# SureDSP_Breakout.net
KiCad netlist of a schematic drawn in EAGLE
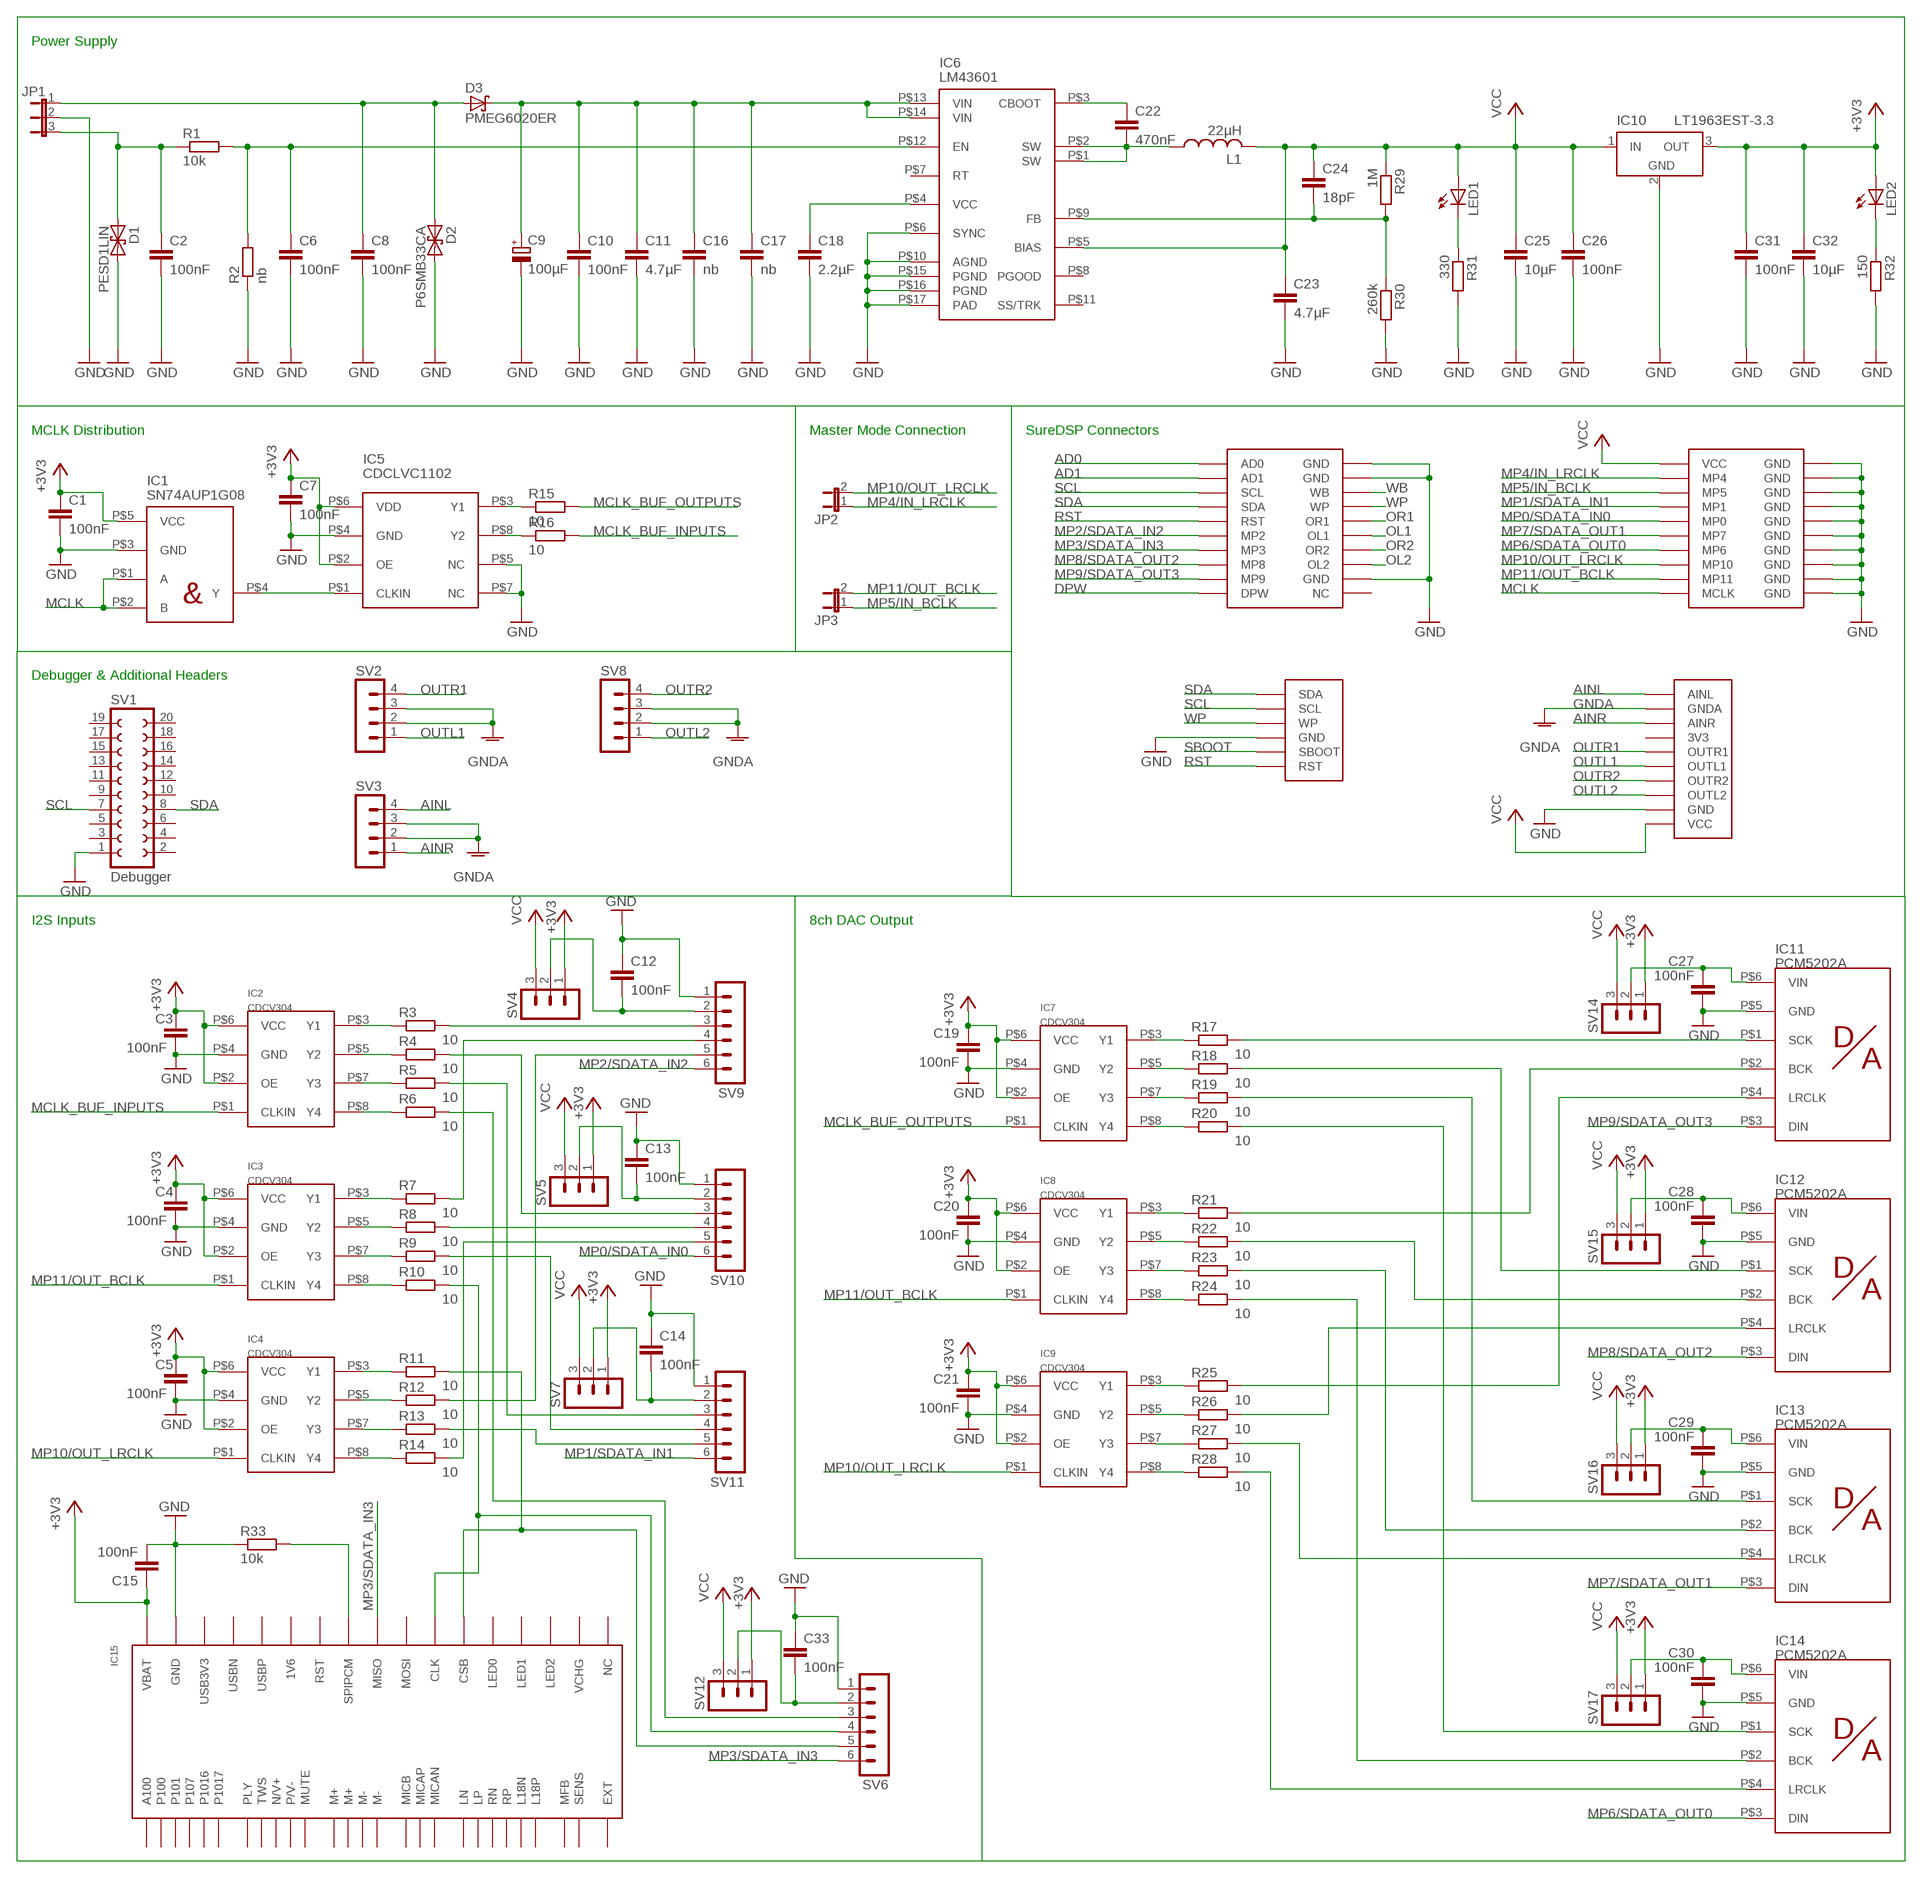
[diagram p0: schematic, sheet 1]

(export (version "E")
  (design (tool "Eeschema 10.0.6"))
  (components
    (comp (ref "C1")
      (value "100nF")
      (footprint "eagle-import:C0805K")
      (libsource (lib "eagle-import") (part "C-EUC0805K"))
    )
    (comp (ref "C2")
      (value "100nF")
      (footprint "eagle-import:C1210K")
      (libsource (lib "eagle-import") (part "C-EUC1210K"))
    )
    (comp (ref "C3")
      (value "100nF")
      (footprint "eagle-import:C0805K")
      (libsource (lib "eagle-import") (part "C-EUC0805K"))
    )
    (comp (ref "C4")
      (value "100nF")
      (footprint "eagle-import:C0805K")
      (libsource (lib "eagle-import") (part "C-EUC0805K"))
    )
    (comp (ref "C5")
      (value "100nF")
      (footprint "eagle-import:C0805K")
      (libsource (lib "eagle-import") (part "C-EUC0805K"))
    )
    (comp (ref "C6")
      (value "100nF")
      (footprint "eagle-import:C1210K")
      (libsource (lib "eagle-import") (part "C-EUC1210K"))
    )
    (comp (ref "C7")
      (value "100nF")
      (footprint "eagle-import:C0805K")
      (libsource (lib "eagle-import") (part "C-EUC0805K"))
    )
    (comp (ref "C8")
      (value "100nF")
      (footprint "eagle-import:C1210K")
      (libsource (lib "eagle-import") (part "C-EUC1210K"))
    )
    (comp (ref "C9")
      (value "100µF")
      (footprint "eagle-import:150CLZ-0810")
      (libsource (lib "eagle-import") (part "CPOL-EU150CLZ-0810"))
    )
    (comp (ref "C10")
      (value "100nF")
      (footprint "eagle-import:C1210K")
      (libsource (lib "eagle-import") (part "C-EUC1210K"))
    )
    (comp (ref "C11")
      (value "4.7µF")
      (footprint "eagle-import:C1210K")
      (libsource (lib "eagle-import") (part "C-EUC1210K"))
    )
    (comp (ref "C12")
      (value "100nF")
      (footprint "eagle-import:C0805K")
      (libsource (lib "eagle-import") (part "C-EUC0805K"))
    )
    (comp (ref "C13")
      (value "100nF")
      (footprint "eagle-import:C0805K")
      (libsource (lib "eagle-import") (part "C-EUC0805K"))
    )
    (comp (ref "C14")
      (value "100nF")
      (footprint "eagle-import:C0805K")
      (libsource (lib "eagle-import") (part "C-EUC0805K"))
    )
    (comp (ref "C15")
      (value "100nF")
      (footprint "eagle-import:C0805K")
      (libsource (lib "eagle-import") (part "C-EUC0805K"))
    )
    (comp (ref "C16")
      (value "nb")
      (footprint "eagle-import:C1210K")
      (libsource (lib "eagle-import") (part "C-EUC1210K"))
    )
    (comp (ref "C17")
      (value "nb")
      (footprint "eagle-import:C1210K")
      (libsource (lib "eagle-import") (part "C-EUC1210K"))
    )
    (comp (ref "C18")
      (value "2.2µF")
      (footprint "eagle-import:C0805K")
      (libsource (lib "eagle-import") (part "C-EUC0805K"))
    )
    (comp (ref "C19")
      (value "100nF")
      (footprint "eagle-import:C0805K")
      (libsource (lib "eagle-import") (part "C-EUC0805K"))
    )
    (comp (ref "C20")
      (value "100nF")
      (footprint "eagle-import:C0805K")
      (libsource (lib "eagle-import") (part "C-EUC0805K"))
    )
    (comp (ref "C21")
      (value "100nF")
      (footprint "eagle-import:C0805K")
      (libsource (lib "eagle-import") (part "C-EUC0805K"))
    )
    (comp (ref "C22")
      (value "470nF")
      (footprint "eagle-import:C0805K")
      (libsource (lib "eagle-import") (part "C-EUC0805K"))
    )
    (comp (ref "C23")
      (value "4.7µF")
      (footprint "eagle-import:C0805K")
      (libsource (lib "eagle-import") (part "C-EUC0805K"))
    )
    (comp (ref "C24")
      (value "18pF")
      (footprint "eagle-import:C0805K")
      (libsource (lib "eagle-import") (part "C-EUC0805K"))
    )
    (comp (ref "C25")
      (value "10µF")
      (footprint "eagle-import:C1210K")
      (libsource (lib "eagle-import") (part "C-EUC1210K"))
    )
    (comp (ref "C26")
      (value "100nF")
      (footprint "eagle-import:C0805K")
      (libsource (lib "eagle-import") (part "C-EUC0805K"))
    )
    (comp (ref "C27")
      (value "100nF")
      (footprint "eagle-import:C0805K")
      (libsource (lib "eagle-import") (part "C-EUC0805K"))
    )
    (comp (ref "C28")
      (value "100nF")
      (footprint "eagle-import:C0805K")
      (libsource (lib "eagle-import") (part "C-EUC0805K"))
    )
    (comp (ref "C29")
      (value "100nF")
      (footprint "eagle-import:C0805K")
      (libsource (lib "eagle-import") (part "C-EUC0805K"))
    )
    (comp (ref "C30")
      (value "100nF")
      (footprint "eagle-import:C0805K")
      (libsource (lib "eagle-import") (part "C-EUC0805K"))
    )
    (comp (ref "C31")
      (value "100nF")
      (footprint "eagle-import:C0805K")
      (libsource (lib "eagle-import") (part "C-EUC0805K"))
    )
    (comp (ref "C32")
      (value "10µF")
      (footprint "eagle-import:C1210K")
      (libsource (lib "eagle-import") (part "C-EUC1210K"))
    )
    (comp (ref "C33")
      (value "100nF")
      (footprint "eagle-import:C0805K")
      (libsource (lib "eagle-import") (part "C-EUC0805K"))
    )
    (comp (ref "D1")
      (value "PESD1LIN")
      (footprint "eagle-import:PESD1LIN")
      (libsource (lib "eagle-import") (part "PESD1LIN"))
    )
    (comp (ref "D2")
      (value "P6SMB33CA")
      (footprint "eagle-import:P6SMB")
      (libsource (lib "eagle-import") (part "P6SMB33CA"))
    )
    (comp (ref "D3")
      (value "PMEG6020ER")
      (footprint "eagle-import:PMEG6020ER")
      (libsource (lib "eagle-import") (part "PMEG6020ER"))
    )
    (comp (ref "IC1")
      (value "SN74AUP1G08")
      (footprint "eagle-import:SN74AUP1G08")
      (libsource (lib "eagle-import") (part "SN74AUP1G08"))
    )
    (comp (ref "IC2")
      (value "CDCV304")
      (footprint "eagle-import:CDCV304")
      (libsource (lib "eagle-import") (part "CDCV304"))
    )
    (comp (ref "IC3")
      (value "CDCV304")
      (footprint "eagle-import:CDCV304")
      (libsource (lib "eagle-import") (part "CDCV304"))
    )
    (comp (ref "IC4")
      (value "CDCV304")
      (footprint "eagle-import:CDCV304")
      (libsource (lib "eagle-import") (part "CDCV304"))
    )
    (comp (ref "IC5")
      (value "CDCLVC1102")
      (footprint "eagle-import:CDCLVC1102")
      (libsource (lib "eagle-import") (part "CDCLVC1102"))
    )
    (comp (ref "IC6")
      (value "LM43601")
      (footprint "eagle-import:LM43601")
      (libsource (lib "eagle-import") (part "LM43601"))
    )
    (comp (ref "IC7")
      (value "CDCV304")
      (footprint "eagle-import:CDCV304")
      (libsource (lib "eagle-import") (part "CDCV304"))
    )
    (comp (ref "IC8")
      (value "CDCV304")
      (footprint "eagle-import:CDCV304")
      (libsource (lib "eagle-import") (part "CDCV304"))
    )
    (comp (ref "IC9")
      (value "CDCV304")
      (footprint "eagle-import:CDCV304")
      (libsource (lib "eagle-import") (part "CDCV304"))
    )
    (comp (ref "IC10")
      (value "LT1963EST-3.3")
      (footprint "eagle-import:SOT223")
      (libsource (lib "eagle-import") (part "LT1963EST-3.3"))
    )
    (comp (ref "IC11")
      (value "PCM5202A")
      (footprint "eagle-import:PCM5202A")
      (libsource (lib "eagle-import") (part "PCM5202A"))
    )
    (comp (ref "IC12")
      (value "PCM5202A")
      (footprint "eagle-import:PCM5202A")
      (libsource (lib "eagle-import") (part "PCM5202A"))
    )
    (comp (ref "IC13")
      (value "PCM5202A")
      (footprint "eagle-import:PCM5202A")
      (libsource (lib "eagle-import") (part "PCM5202A"))
    )
    (comp (ref "IC14")
      (value "PCM5202A")
      (footprint "eagle-import:PCM5202A")
      (libsource (lib "eagle-import") (part "PCM5202A"))
    )
    (comp (ref "IC15")
      (value "CSRA64215")
      (footprint "eagle-import:CSRA64215")
      (libsource (lib "eagle-import") (part "CSRA64215"))
    )
    (comp (ref "IC16")
      (value "SUREDSP")
      (footprint "eagle-import:SUREDSP")
      (libsource (lib "eagle-import") (part "SUREDSP"))
    )
    (comp (ref "JP1")
      (value "JP2E")
      (footprint "eagle-import:JP2")
      (libsource (lib "eagle-import") (part "JP2E"))
    )
    (comp (ref "JP2")
      (value "JP1E")
      (footprint "eagle-import:JP1")
      (libsource (lib "eagle-import") (part "JP1E"))
    )
    (comp (ref "JP3")
      (value "JP1E")
      (footprint "eagle-import:JP1")
      (libsource (lib "eagle-import") (part "JP1E"))
    )
    (comp (ref "L1")
      (value "22µH")
      (footprint "eagle-import:L5650M")
      (libsource (lib "eagle-import") (part "L-USL5650M"))
    )
    (comp (ref "LED1")
      (value "LEDSML0805")
      (footprint "eagle-import:SML0805")
      (libsource (lib "eagle-import") (part "LEDSML0805"))
    )
    (comp (ref "LED2")
      (value "LEDSML0805")
      (footprint "eagle-import:SML0805")
      (libsource (lib "eagle-import") (part "LEDSML0805"))
    )
    (comp (ref "R1")
      (value "10k")
      (footprint "eagle-import:R2012")
      (libsource (lib "eagle-import") (part "R-EU_R2012"))
    )
    (comp (ref "R2")
      (value "nb")
      (footprint "eagle-import:R2012")
      (libsource (lib "eagle-import") (part "R-EU_R2012"))
    )
    (comp (ref "R3")
      (value "10")
      (footprint "eagle-import:R2012")
      (libsource (lib "eagle-import") (part "R-EU_R2012"))
    )
    (comp (ref "R4")
      (value "10")
      (footprint "eagle-import:R2012")
      (libsource (lib "eagle-import") (part "R-EU_R2012"))
    )
    (comp (ref "R5")
      (value "10")
      (footprint "eagle-import:R2012")
      (libsource (lib "eagle-import") (part "R-EU_R2012"))
    )
    (comp (ref "R6")
      (value "10")
      (footprint "eagle-import:R2012")
      (libsource (lib "eagle-import") (part "R-EU_R2012"))
    )
    (comp (ref "R7")
      (value "10")
      (footprint "eagle-import:R2012")
      (libsource (lib "eagle-import") (part "R-EU_R2012"))
    )
    (comp (ref "R8")
      (value "10")
      (footprint "eagle-import:R2012")
      (libsource (lib "eagle-import") (part "R-EU_R2012"))
    )
    (comp (ref "R9")
      (value "10")
      (footprint "eagle-import:R2012")
      (libsource (lib "eagle-import") (part "R-EU_R2012"))
    )
    (comp (ref "R10")
      (value "10")
      (footprint "eagle-import:R2012")
      (libsource (lib "eagle-import") (part "R-EU_R2012"))
    )
    (comp (ref "R11")
      (value "10")
      (footprint "eagle-import:R2012")
      (libsource (lib "eagle-import") (part "R-EU_R2012"))
    )
    (comp (ref "R12")
      (value "10")
      (footprint "eagle-import:R2012")
      (libsource (lib "eagle-import") (part "R-EU_R2012"))
    )
    (comp (ref "R13")
      (value "10")
      (footprint "eagle-import:R2012")
      (libsource (lib "eagle-import") (part "R-EU_R2012"))
    )
    (comp (ref "R14")
      (value "10")
      (footprint "eagle-import:R2012")
      (libsource (lib "eagle-import") (part "R-EU_R2012"))
    )
    (comp (ref "R15")
      (value "10")
      (footprint "eagle-import:R2012")
      (libsource (lib "eagle-import") (part "R-EU_R2012"))
    )
    (comp (ref "R16")
      (value "10")
      (footprint "eagle-import:R2012")
      (libsource (lib "eagle-import") (part "R-EU_R2012"))
    )
    (comp (ref "R17")
      (value "10")
      (footprint "eagle-import:R2012")
      (libsource (lib "eagle-import") (part "R-EU_R2012"))
    )
    (comp (ref "R18")
      (value "10")
      (footprint "eagle-import:R2012")
      (libsource (lib "eagle-import") (part "R-EU_R2012"))
    )
    (comp (ref "R19")
      (value "10")
      (footprint "eagle-import:R2012")
      (libsource (lib "eagle-import") (part "R-EU_R2012"))
    )
    (comp (ref "R20")
      (value "10")
      (footprint "eagle-import:R2012")
      (libsource (lib "eagle-import") (part "R-EU_R2012"))
    )
    (comp (ref "R21")
      (value "10")
      (footprint "eagle-import:R2012")
      (libsource (lib "eagle-import") (part "R-EU_R2012"))
    )
    (comp (ref "R22")
      (value "10")
      (footprint "eagle-import:R2012")
      (libsource (lib "eagle-import") (part "R-EU_R2012"))
    )
    (comp (ref "R23")
      (value "10")
      (footprint "eagle-import:R2012")
      (libsource (lib "eagle-import") (part "R-EU_R2012"))
    )
    (comp (ref "R24")
      (value "10")
      (footprint "eagle-import:R2012")
      (libsource (lib "eagle-import") (part "R-EU_R2012"))
    )
    (comp (ref "R25")
      (value "10")
      (footprint "eagle-import:R2012")
      (libsource (lib "eagle-import") (part "R-EU_R2012"))
    )
    (comp (ref "R26")
      (value "10")
      (footprint "eagle-import:R2012")
      (libsource (lib "eagle-import") (part "R-EU_R2012"))
    )
    (comp (ref "R27")
      (value "10")
      (footprint "eagle-import:R2012")
      (libsource (lib "eagle-import") (part "R-EU_R2012"))
    )
    (comp (ref "R28")
      (value "10")
      (footprint "eagle-import:R2012")
      (libsource (lib "eagle-import") (part "R-EU_R2012"))
    )
    (comp (ref "R29")
      (value "1M")
      (footprint "eagle-import:R2012")
      (libsource (lib "eagle-import") (part "R-EU_R2012"))
    )
    (comp (ref "R30")
      (value "260k")
      (footprint "eagle-import:R2012")
      (libsource (lib "eagle-import") (part "R-EU_R2012"))
    )
    (comp (ref "R31")
      (value "330")
      (footprint "eagle-import:R2012")
      (libsource (lib "eagle-import") (part "R-EU_R2012"))
    )
    (comp (ref "R32")
      (value "150")
      (footprint "eagle-import:R2012")
      (libsource (lib "eagle-import") (part "R-EU_R2012"))
    )
    (comp (ref "R33")
      (value "10k")
      (footprint "eagle-import:R2012")
      (libsource (lib "eagle-import") (part "R-EU_R2012"))
    )
    (comp (ref "SV1")
      (value "Debugger")
      (footprint "eagle-import:FE10-2")
      (libsource (lib "eagle-import") (part "FE10-2"))
    )
    (comp (ref "SV2")
      (value "MA04-1")
      (footprint "eagle-import:MA04-1")
      (libsource (lib "eagle-import") (part "MA04-1"))
    )
    (comp (ref "SV3")
      (value "MA04-1")
      (footprint "eagle-import:MA04-1")
      (libsource (lib "eagle-import") (part "MA04-1"))
    )
    (comp (ref "SV4")
      (value "MA03-1")
      (footprint "eagle-import:MA03-1")
      (libsource (lib "eagle-import") (part "MA03-1"))
    )
    (comp (ref "SV5")
      (value "MA03-1")
      (footprint "eagle-import:MA03-1")
      (libsource (lib "eagle-import") (part "MA03-1"))
    )
    (comp (ref "SV6")
      (value "MA06-1")
      (footprint "eagle-import:MA06-1")
      (libsource (lib "eagle-import") (part "MA06-1"))
    )
    (comp (ref "SV7")
      (value "MA03-1")
      (footprint "eagle-import:MA03-1")
      (libsource (lib "eagle-import") (part "MA03-1"))
    )
    (comp (ref "SV8")
      (value "MA04-1")
      (footprint "eagle-import:MA04-1")
      (libsource (lib "eagle-import") (part "MA04-1"))
    )
    (comp (ref "SV9")
      (value "MA06-1")
      (footprint "eagle-import:MA06-1")
      (libsource (lib "eagle-import") (part "MA06-1"))
    )
    (comp (ref "SV10")
      (value "MA06-1")
      (footprint "eagle-import:MA06-1")
      (libsource (lib "eagle-import") (part "MA06-1"))
    )
    (comp (ref "SV11")
      (value "MA06-1")
      (footprint "eagle-import:MA06-1")
      (libsource (lib "eagle-import") (part "MA06-1"))
    )
    (comp (ref "SV12")
      (value "MA03-1")
      (footprint "eagle-import:MA03-1")
      (libsource (lib "eagle-import") (part "MA03-1"))
    )
    (comp (ref "SV14")
      (value "MA03-1")
      (footprint "eagle-import:MA03-1")
      (libsource (lib "eagle-import") (part "MA03-1"))
    )
    (comp (ref "SV15")
      (value "MA03-1")
      (footprint "eagle-import:MA03-1")
      (libsource (lib "eagle-import") (part "MA03-1"))
    )
    (comp (ref "SV16")
      (value "MA03-1")
      (footprint "eagle-import:MA03-1")
      (libsource (lib "eagle-import") (part "MA03-1"))
    )
    (comp (ref "SV17")
      (value "MA03-1")
      (footprint "eagle-import:MA03-1")
      (libsource (lib "eagle-import") (part "MA03-1"))
    )
  )
  (nets
    (net (code "1") (name "+3V3") (class "Default")
      (node (ref "C1") (pin "1") (pinfunction "1_1") (pintype "passive"))
      (node (ref "C15") (pin "1") (pinfunction "1_1") (pintype "passive"))
      (node (ref "C19") (pin "1") (pinfunction "1_1") (pintype "passive"))
      (node (ref "C20") (pin "1") (pinfunction "1_1") (pintype "passive"))
      (node (ref "C21") (pin "1") (pinfunction "1_1") (pintype "passive"))
      (node (ref "C3") (pin "1") (pinfunction "1_1") (pintype "passive"))
      (node (ref "C31") (pin "1") (pinfunction "1_1") (pintype "passive"))
      (node (ref "C32") (pin "1") (pinfunction "1_1") (pintype "passive"))
      (node (ref "C4") (pin "1") (pinfunction "1_1") (pintype "passive"))
      (node (ref "C5") (pin "1") (pinfunction "1_1") (pintype "passive"))
      (node (ref "C7") (pin "1") (pinfunction "1_1") (pintype "passive"))
      (node (ref "IC1") (pin "P$5") (pinfunction "VCC_P$5") (pintype "bidirectional"))
      (node (ref "IC10") (pin "3") (pinfunction "OUT_3") (pintype "output"))
      (node (ref "IC15") (pin "P$5") (pinfunction "VBAT_P$5") (pintype "bidirectional"))
      (node (ref "IC2") (pin "P$2") (pinfunction "OE_P$2") (pintype "bidirectional"))
      (node (ref "IC2") (pin "P$6") (pinfunction "VCC_P$6") (pintype "bidirectional"))
      (node (ref "IC3") (pin "P$2") (pinfunction "OE_P$2") (pintype "bidirectional"))
      (node (ref "IC3") (pin "P$6") (pinfunction "VCC_P$6") (pintype "bidirectional"))
      (node (ref "IC4") (pin "P$2") (pinfunction "OE_P$2") (pintype "bidirectional"))
      (node (ref "IC4") (pin "P$6") (pinfunction "VCC_P$6") (pintype "bidirectional"))
      (node (ref "IC5") (pin "P$2") (pinfunction "OE_P$2") (pintype "bidirectional"))
      (node (ref "IC5") (pin "P$6") (pinfunction "VDD_P$6") (pintype "bidirectional"))
      (node (ref "IC7") (pin "P$2") (pinfunction "OE_P$2") (pintype "bidirectional"))
      (node (ref "IC7") (pin "P$6") (pinfunction "VCC_P$6") (pintype "bidirectional"))
      (node (ref "IC8") (pin "P$2") (pinfunction "OE_P$2") (pintype "bidirectional"))
      (node (ref "IC8") (pin "P$6") (pinfunction "VCC_P$6") (pintype "bidirectional"))
      (node (ref "IC9") (pin "P$2") (pinfunction "OE_P$2") (pintype "bidirectional"))
      (node (ref "IC9") (pin "P$6") (pinfunction "VCC_P$6") (pintype "bidirectional"))
      (node (ref "LED2") (pin "A") (pinfunction "A_A") (pintype "passive"))
      (node (ref "SV12") (pin "1") (pinfunction "1_1") (pintype "passive"))
      (node (ref "SV14") (pin "1") (pinfunction "1_1") (pintype "passive"))
      (node (ref "SV15") (pin "1") (pinfunction "1_1") (pintype "passive"))
      (node (ref "SV16") (pin "1") (pinfunction "1_1") (pintype "passive"))
      (node (ref "SV17") (pin "1") (pinfunction "1_1") (pintype "passive"))
      (node (ref "SV4") (pin "1") (pinfunction "1_1") (pintype "passive"))
      (node (ref "SV5") (pin "1") (pinfunction "1_1") (pintype "passive"))
      (node (ref "SV7") (pin "1") (pinfunction "1_1") (pintype "passive"))
    )
    (net (code "2") (name "/AD0") (class "Default")
      (node (ref "IC16") (pin "AD0") (pinfunction "AD0_AD0") (pintype "bidirectional"))
    )
    (net (code "3") (name "/AD1") (class "Default")
      (node (ref "IC16") (pin "AD1") (pinfunction "AD1_AD1") (pintype "bidirectional"))
    )
    (net (code "4") (name "/AINL") (class "Default")
      (node (ref "IC16") (pin "AINL") (pinfunction "AINL_AINL") (pintype "bidirectional"))
      (node (ref "SV3") (pin "4") (pinfunction "4_4") (pintype "passive"))
    )
    (net (code "5") (name "/AINR") (class "Default")
      (node (ref "IC16") (pin "AINR") (pinfunction "AINR_AINR") (pintype "bidirectional"))
      (node (ref "SV3") (pin "1") (pinfunction "1_1") (pintype "passive"))
    )
    (net (code "6") (name "/DPW") (class "Default")
      (node (ref "IC16") (pin "DPW") (pinfunction "DPW_DPW") (pintype "bidirectional"))
    )
    (net (code "7") (name "/MCLK") (class "Default")
      (node (ref "IC1") (pin "P$1") (pinfunction "A_P$1") (pintype "bidirectional"))
      (node (ref "IC1") (pin "P$2") (pinfunction "B_P$2") (pintype "bidirectional"))
      (node (ref "IC16") (pin "MCLK") (pinfunction "MCLK_MCLK") (pintype "bidirectional"))
    )
    (net (code "8") (name "/MCLK_BUF_INPUTS") (class "Default")
      (node (ref "IC2") (pin "P$1") (pinfunction "CLKIN_P$1") (pintype "bidirectional"))
      (node (ref "R16") (pin "2") (pinfunction "2_2") (pintype "passive"))
    )
    (net (code "9") (name "/MCLK_BUF_OUTPUTS") (class "Default")
      (node (ref "IC7") (pin "P$1") (pinfunction "CLKIN_P$1") (pintype "bidirectional"))
      (node (ref "R15") (pin "2") (pinfunction "2_2") (pintype "passive"))
    )
    (net (code "10") (name "/MP0{slash}SDATA_IN0") (class "Default")
      (node (ref "IC16") (pin "MP0") (pinfunction "MP0_MP0") (pintype "bidirectional"))
      (node (ref "SV10") (pin "6") (pinfunction "6_6") (pintype "passive"))
    )
    (net (code "11") (name "/MP1{slash}SDATA_IN1") (class "Default")
      (node (ref "IC16") (pin "MP1") (pinfunction "MP1_MP1") (pintype "bidirectional"))
      (node (ref "SV11") (pin "6") (pinfunction "6_6") (pintype "passive"))
    )
    (net (code "12") (name "/MP2{slash}SDATA_IN2") (class "Default")
      (node (ref "IC16") (pin "MP2") (pinfunction "MP2_MP2") (pintype "bidirectional"))
      (node (ref "SV9") (pin "6") (pinfunction "6_6") (pintype "passive"))
    )
    (net (code "13") (name "/MP3{slash}SDATA_IN3") (class "Default")
      (node (ref "IC15") (pin "P$7") (pinfunction "MISO_P$7") (pintype "bidirectional"))
      (node (ref "IC16") (pin "MP3") (pinfunction "MP3_MP3") (pintype "bidirectional"))
      (node (ref "SV6") (pin "6") (pinfunction "6_6") (pintype "passive"))
    )
    (net (code "14") (name "/MP4{slash}IN_LRCLK") (class "Default")
      (node (ref "IC16") (pin "MP4") (pinfunction "MP4_MP4") (pintype "bidirectional"))
      (node (ref "JP2") (pin "1") (pinfunction "1_1") (pintype "passive"))
    )
    (net (code "15") (name "/MP5{slash}IN_BCLK") (class "Default")
      (node (ref "IC16") (pin "MP5") (pinfunction "MP5_MP5") (pintype "bidirectional"))
      (node (ref "JP3") (pin "1") (pinfunction "1_1") (pintype "passive"))
    )
    (net (code "16") (name "/MP6{slash}SDATA_OUT0") (class "Default")
      (node (ref "IC14") (pin "P$3") (pinfunction "DIN_P$3") (pintype "bidirectional"))
      (node (ref "IC16") (pin "MP6") (pinfunction "MP6_MP6") (pintype "bidirectional"))
    )
    (net (code "17") (name "/MP7{slash}SDATA_OUT1") (class "Default")
      (node (ref "IC13") (pin "P$3") (pinfunction "DIN_P$3") (pintype "bidirectional"))
      (node (ref "IC16") (pin "MP7") (pinfunction "MP7_MP7") (pintype "bidirectional"))
    )
    (net (code "18") (name "/MP8{slash}SDATA_OUT2") (class "Default")
      (node (ref "IC12") (pin "P$3") (pinfunction "DIN_P$3") (pintype "bidirectional"))
      (node (ref "IC16") (pin "MP8") (pinfunction "MP8_MP8") (pintype "bidirectional"))
    )
    (net (code "19") (name "/MP9{slash}SDATA_OUT3") (class "Default")
      (node (ref "IC11") (pin "P$3") (pinfunction "DIN_P$3") (pintype "bidirectional"))
      (node (ref "IC16") (pin "MP9") (pinfunction "MP9_MP9") (pintype "bidirectional"))
    )
    (net (code "20") (name "/MP10{slash}OUT_LRCLK") (class "Default")
      (node (ref "IC16") (pin "MP10") (pinfunction "MP10_MP10") (pintype "bidirectional"))
      (node (ref "IC4") (pin "P$1") (pinfunction "CLKIN_P$1") (pintype "bidirectional"))
      (node (ref "IC9") (pin "P$1") (pinfunction "CLKIN_P$1") (pintype "bidirectional"))
      (node (ref "JP2") (pin "2") (pinfunction "2_2") (pintype "passive"))
    )
    (net (code "21") (name "/MP11{slash}OUT_BCLK") (class "Default")
      (node (ref "IC16") (pin "MP11") (pinfunction "MP11_MP11") (pintype "bidirectional"))
      (node (ref "IC3") (pin "P$1") (pinfunction "CLKIN_P$1") (pintype "bidirectional"))
      (node (ref "IC8") (pin "P$1") (pinfunction "CLKIN_P$1") (pintype "bidirectional"))
      (node (ref "JP3") (pin "2") (pinfunction "2_2") (pintype "passive"))
    )
    (net (code "22") (name "/OL1") (class "Default")
      (node (ref "IC16") (pin "OL1") (pinfunction "OL1_OL1") (pintype "bidirectional"))
    )
    (net (code "23") (name "/OL2") (class "Default")
      (node (ref "IC16") (pin "OL2") (pinfunction "OL2_OL2") (pintype "bidirectional"))
    )
    (net (code "24") (name "/OR1") (class "Default")
      (node (ref "IC16") (pin "OR1") (pinfunction "OR1_OR1") (pintype "bidirectional"))
    )
    (net (code "25") (name "/OR2") (class "Default")
      (node (ref "IC16") (pin "OR2") (pinfunction "OR2_OR2") (pintype "bidirectional"))
    )
    (net (code "26") (name "/OUTL1") (class "Default")
      (node (ref "IC16") (pin "OUTL1") (pinfunction "OUTL1_OUTL1") (pintype "bidirectional"))
      (node (ref "SV2") (pin "1") (pinfunction "1_1") (pintype "passive"))
    )
    (net (code "27") (name "/OUTL2") (class "Default")
      (node (ref "IC16") (pin "OUTL2") (pinfunction "OUTL2_OUTL2") (pintype "bidirectional"))
      (node (ref "SV8") (pin "1") (pinfunction "1_1") (pintype "passive"))
    )
    (net (code "28") (name "/OUTR1") (class "Default")
      (node (ref "IC16") (pin "OUTR1") (pinfunction "OUTR1_OUTR1") (pintype "bidirectional"))
      (node (ref "SV2") (pin "4") (pinfunction "4_4") (pintype "passive"))
    )
    (net (code "29") (name "/OUTR2") (class "Default")
      (node (ref "IC16") (pin "OUTR2") (pinfunction "OUTR2_OUTR2") (pintype "bidirectional"))
      (node (ref "SV8") (pin "4") (pinfunction "4_4") (pintype "passive"))
    )
    (net (code "30") (name "/RST") (class "Default")
      (node (ref "IC16") (pin "RESET") (pinfunction "RST_RESET") (pintype "bidirectional"))
      (node (ref "IC16") (pin "RST") (pinfunction "RST_RST") (pintype "bidirectional"))
    )
    (net (code "31") (name "/SBOOT") (class "Default")
      (node (ref "IC16") (pin "SBOOT") (pinfunction "SBOOT_SBOOT") (pintype "bidirectional"))
    )
    (net (code "32") (name "/SCL") (class "Default")
      (node (ref "IC16") (pin "SCL") (pinfunction "SCL_SCL") (pintype "bidirectional"))
      (node (ref "IC16") (pin "SCL20ER") (pinfunction "SCL_SCL20ER") (pintype "bidirectional"))
      (node (ref "SV1") (pin "7") (pinfunction "7_7") (pintype "passive"))
    )
    (net (code "33") (name "/SDA") (class "Default")
      (node (ref "IC16") (pin "SDA") (pinfunction "SDA_SDA") (pintype "bidirectional"))
      (node (ref "IC16") (pin "SDA20ER") (pinfunction "SDA_SDA20ER") (pintype "bidirectional"))
      (node (ref "SV1") (pin "8") (pinfunction "8_8") (pintype "passive"))
    )
    (net (code "34") (name "/WB") (class "Default")
      (node (ref "IC16") (pin "WB") (pinfunction "WB_WB") (pintype "bidirectional"))
    )
    (net (code "35") (name "/WP") (class "Default")
      (node (ref "IC16") (pin "WP") (pinfunction "WP_WP") (pintype "bidirectional"))
      (node (ref "IC16") (pin "WP20ER") (pinfunction "WP_WP20ER") (pintype "bidirectional"))
    )
    (net (code "36") (name "GND") (class "Default")
      (node (ref "C1") (pin "2") (pinfunction "2_2") (pintype "passive"))
      (node (ref "C10") (pin "2") (pinfunction "2_2") (pintype "passive"))
      (node (ref "C11") (pin "2") (pinfunction "2_2") (pintype "passive"))
      (node (ref "C12") (pin "1") (pinfunction "1_1") (pintype "passive"))
      (node (ref "C13") (pin "1") (pinfunction "1_1") (pintype "passive"))
      (node (ref "C14") (pin "1") (pinfunction "1_1") (pintype "passive"))
      (node (ref "C15") (pin "2") (pinfunction "2_2") (pintype "passive"))
      (node (ref "C16") (pin "2") (pinfunction "2_2") (pintype "passive"))
      (node (ref "C17") (pin "2") (pinfunction "2_2") (pintype "passive"))
      (node (ref "C18") (pin "2") (pinfunction "2_2") (pintype "passive"))
      (node (ref "C19") (pin "2") (pinfunction "2_2") (pintype "passive"))
      (node (ref "C2") (pin "2") (pinfunction "2_2") (pintype "passive"))
      (node (ref "C20") (pin "2") (pinfunction "2_2") (pintype "passive"))
      (node (ref "C21") (pin "2") (pinfunction "2_2") (pintype "passive"))
      (node (ref "C23") (pin "2") (pinfunction "2_2") (pintype "passive"))
      (node (ref "C25") (pin "2") (pinfunction "2_2") (pintype "passive"))
      (node (ref "C26") (pin "2") (pinfunction "2_2") (pintype "passive"))
      (node (ref "C27") (pin "2") (pinfunction "2_2") (pintype "passive"))
      (node (ref "C28") (pin "2") (pinfunction "2_2") (pintype "passive"))
      (node (ref "C29") (pin "2") (pinfunction "2_2") (pintype "passive"))
      (node (ref "C3") (pin "2") (pinfunction "2_2") (pintype "passive"))
      (node (ref "C30") (pin "2") (pinfunction "2_2") (pintype "passive"))
      (node (ref "C31") (pin "2") (pinfunction "2_2") (pintype "passive"))
      (node (ref "C32") (pin "2") (pinfunction "2_2") (pintype "passive"))
      (node (ref "C33") (pin "1") (pinfunction "1_1") (pintype "passive"))
      (node (ref "C4") (pin "2") (pinfunction "2_2") (pintype "passive"))
      (node (ref "C5") (pin "2") (pinfunction "2_2") (pintype "passive"))
      (node (ref "C6") (pin "2") (pinfunction "2_2") (pintype "passive"))
      (node (ref "C7") (pin "2") (pinfunction "2_2") (pintype "passive"))
      (node (ref "C8") (pin "2") (pinfunction "2_2") (pintype "passive"))
      (node (ref "C9") (pin "-") (pinfunction "-_-") (pintype "passive"))
      (node (ref "D1") (pin "P$2") (pinfunction "2_P$2") (pintype "passive"))
      (node (ref "D2") (pin "P$2") (pinfunction "2_P$2") (pintype "passive"))
      (node (ref "IC1") (pin "P$3") (pinfunction "GND_P$3") (pintype "bidirectional"))
      (node (ref "IC10") (pin "2") (pinfunction "GND_2") (pintype "power_in"))
      (node (ref "IC11") (pin "P$5") (pinfunction "GND_P$5") (pintype "bidirectional"))
      (node (ref "IC12") (pin "P$5") (pinfunction "GND_P$5") (pintype "bidirectional"))
      (node (ref "IC13") (pin "P$5") (pinfunction "GND_P$5") (pintype "bidirectional"))
      (node (ref "IC14") (pin "P$5") (pinfunction "GND_P$5") (pintype "bidirectional"))
      (node (ref "IC15") (pin "P$6") (pinfunction "GND_P$6") (pintype "bidirectional"))
      (node (ref "IC16") (pin "GND10ER") (pinfunction "GND_GND10ER") (pintype "bidirectional"))
      (node (ref "IC16") (pin "GND20ER") (pinfunction "GND_GND20ER") (pintype "bidirectional"))
      (node (ref "IC16") (pin "GND20ER1") (pinfunction "GND_GND20ER1") (pintype "bidirectional"))
      (node (ref "IC16") (pin "GND20ER2") (pinfunction "GND_GND20ER2") (pintype "bidirectional"))
      (node (ref "IC16") (pin "GND6ER") (pinfunction "GND_GND6ER") (pintype "bidirectional"))
      (node (ref "IC16") (pin "P$10") (pinfunction "GND_P$10") (pintype "bidirectional"))
      (node (ref "IC16") (pin "P$12") (pinfunction "GND_P$12") (pintype "bidirectional"))
      (node (ref "IC16") (pin "P$14") (pinfunction "GND_P$14") (pintype "bidirectional"))
      (node (ref "IC16") (pin "P$16") (pinfunction "GND_P$16") (pintype "bidirectional"))
      (node (ref "IC16") (pin "P$18") (pinfunction "GND_P$18") (pintype "bidirectional"))
      (node (ref "IC16") (pin "P$2") (pinfunction "GND_P$2") (pintype "bidirectional"))
      (node (ref "IC16") (pin "P$3") (pinfunction "GND_P$3") (pintype "bidirectional"))
      (node (ref "IC16") (pin "P$55") (pinfunction "GND_P$55") (pintype "bidirectional"))
      (node (ref "IC16") (pin "P$6") (pinfunction "GND_P$6") (pintype "bidirectional"))
      (node (ref "IC16") (pin "P$8") (pinfunction "GND_P$8") (pintype "bidirectional"))
      (node (ref "IC2") (pin "P$4") (pinfunction "GND_P$4") (pintype "bidirectional"))
      (node (ref "IC3") (pin "P$4") (pinfunction "GND_P$4") (pintype "bidirectional"))
      (node (ref "IC4") (pin "P$4") (pinfunction "GND_P$4") (pintype "bidirectional"))
      (node (ref "IC5") (pin "P$4") (pinfunction "GND_P$4") (pintype "bidirectional"))
      (node (ref "IC5") (pin "P$5") (pinfunction "NC_P$5") (pintype "bidirectional"))
      (node (ref "IC5") (pin "P$7") (pinfunction "NC_P$7") (pintype "bidirectional"))
      (node (ref "IC6") (pin "P$10") (pinfunction "AGND_P$10") (pintype "bidirectional"))
      (node (ref "IC6") (pin "P$15") (pinfunction "PGND_P$15") (pintype "bidirectional"))
      (node (ref "IC6") (pin "P$16") (pinfunction "PGND_P$16") (pintype "bidirectional"))
      (node (ref "IC6") (pin "P$17") (pinfunction "PAD_P$17") (pintype "bidirectional"))
      (node (ref "IC6") (pin "P$6") (pinfunction "SYNC_P$6") (pintype "bidirectional"))
      (node (ref "IC7") (pin "P$4") (pinfunction "GND_P$4") (pintype "bidirectional"))
      (node (ref "IC8") (pin "P$4") (pinfunction "GND_P$4") (pintype "bidirectional"))
      (node (ref "IC9") (pin "P$4") (pinfunction "GND_P$4") (pintype "bidirectional"))
      (node (ref "JP1") (pin "2") (pinfunction "2_2") (pintype "passive"))
      (node (ref "R2") (pin "1") (pinfunction "1_1") (pintype "passive"))
      (node (ref "R30") (pin "2") (pinfunction "2_2") (pintype "passive"))
      (node (ref "R31") (pin "2") (pinfunction "2_2") (pintype "passive"))
      (node (ref "R32") (pin "2") (pinfunction "2_2") (pintype "passive"))
      (node (ref "R33") (pin "1") (pinfunction "1_1") (pintype "passive"))
      (node (ref "SV1") (pin "1") (pinfunction "1_1") (pintype "passive"))
      (node (ref "SV10") (pin "1") (pinfunction "1_1") (pintype "passive"))
      (node (ref "SV11") (pin "1") (pinfunction "1_1") (pintype "passive"))
      (node (ref "SV6") (pin "1") (pinfunction "1_1") (pintype "passive"))
      (node (ref "SV9") (pin "1") (pinfunction "1_1") (pintype "passive"))
    )
    (net (code "37") (name "GNDA") (class "Default")
      (node (ref "IC16") (pin "AGND") (pinfunction "GNDA_AGND") (pintype "bidirectional"))
      (node (ref "SV2") (pin "2") (pinfunction "2_2") (pintype "passive"))
      (node (ref "SV2") (pin "3") (pinfunction "3_3") (pintype "passive"))
      (node (ref "SV3") (pin "2") (pinfunction "2_2") (pintype "passive"))
      (node (ref "SV3") (pin "3") (pinfunction "3_3") (pintype "passive"))
      (node (ref "SV8") (pin "2") (pinfunction "2_2") (pintype "passive"))
      (node (ref "SV8") (pin "3") (pinfunction "3_3") (pintype "passive"))
    )
    (net (code "38") (name "Net-(C12-Pad2)") (class "Default")
      (node (ref "C12") (pin "2") (pinfunction "2_2") (pintype "passive"))
      (node (ref "SV4") (pin "2") (pinfunction "2_2") (pintype "passive"))
      (node (ref "SV9") (pin "2") (pinfunction "2_2") (pintype "passive"))
    )
    (net (code "39") (name "Net-(C13-Pad2)") (class "Default")
      (node (ref "C13") (pin "2") (pinfunction "2_2") (pintype "passive"))
      (node (ref "SV10") (pin "2") (pinfunction "2_2") (pintype "passive"))
      (node (ref "SV5") (pin "2") (pinfunction "2_2") (pintype "passive"))
    )
    (net (code "40") (name "Net-(C14-Pad2)") (class "Default")
      (node (ref "C14") (pin "2") (pinfunction "2_2") (pintype "passive"))
      (node (ref "SV11") (pin "2") (pinfunction "2_2") (pintype "passive"))
      (node (ref "SV7") (pin "2") (pinfunction "2_2") (pintype "passive"))
    )
    (net (code "41") (name "Net-(C22-Pad2)") (class "Default")
      (node (ref "C22") (pin "2") (pinfunction "2_2") (pintype "passive"))
      (node (ref "IC6") (pin "P$1") (pinfunction "SW_P$1") (pintype "bidirectional"))
      (node (ref "IC6") (pin "P$2") (pinfunction "SW_P$2") (pintype "bidirectional"))
      (node (ref "L1") (pin "1") (pinfunction "1_1") (pintype "passive"))
    )
    (net (code "42") (name "Net-(C33-Pad2)") (class "Default")
      (node (ref "C33") (pin "2") (pinfunction "2_2") (pintype "passive"))
      (node (ref "SV12") (pin "2") (pinfunction "2_2") (pintype "passive"))
      (node (ref "SV6") (pin "2") (pinfunction "2_2") (pintype "passive"))
    )
    (net (code "43") (name "Net-(D1-1)") (class "Default")
      (node (ref "C2") (pin "1") (pinfunction "1_1") (pintype "passive"))
      (node (ref "D1") (pin "P$1") (pinfunction "1_P$1") (pintype "passive"))
      (node (ref "JP1") (pin "3") (pinfunction "3_3") (pintype "passive"))
      (node (ref "R1") (pin "1") (pinfunction "1_1") (pintype "passive"))
    )
    (net (code "44") (name "Net-(D2-1)") (class "Default")
      (node (ref "C8") (pin "1") (pinfunction "1_1") (pintype "passive"))
      (node (ref "D2") (pin "P$1") (pinfunction "1_P$1") (pintype "passive"))
      (node (ref "D3") (pin "P$1") (pinfunction "A_P$1") (pintype "passive"))
      (node (ref "JP1") (pin "1") (pinfunction "1_1") (pintype "passive"))
    )
    (net (code "45") (name "Net-(D3-C)") (class "Default")
      (node (ref "C10") (pin "1") (pinfunction "1_1") (pintype "passive"))
      (node (ref "C11") (pin "1") (pinfunction "1_1") (pintype "passive"))
      (node (ref "C16") (pin "1") (pinfunction "1_1") (pintype "passive"))
      (node (ref "C17") (pin "1") (pinfunction "1_1") (pintype "passive"))
      (node (ref "C9") (pin "+") (pinfunction "+_+") (pintype "passive"))
      (node (ref "D3") (pin "P$2") (pinfunction "C_P$2") (pintype "passive"))
      (node (ref "IC6") (pin "P$13") (pinfunction "VIN_P$13") (pintype "bidirectional"))
      (node (ref "IC6") (pin "P$14") (pinfunction "VIN_P$14") (pintype "bidirectional"))
    )
    (net (code "46") (name "Net-(IC1-Y)") (class "Default")
      (node (ref "IC1") (pin "P$4") (pinfunction "Y_P$4") (pintype "bidirectional"))
      (node (ref "IC5") (pin "P$1") (pinfunction "CLKIN_P$1") (pintype "bidirectional"))
    )
    (net (code "47") (name "Net-(IC2-Y1)") (class "Default")
      (node (ref "IC2") (pin "P$3") (pinfunction "Y1_P$3") (pintype "bidirectional"))
      (node (ref "R3") (pin "1") (pinfunction "1_1") (pintype "passive"))
    )
    (net (code "48") (name "Net-(IC2-Y2)") (class "Default")
      (node (ref "IC2") (pin "P$5") (pinfunction "Y2_P$5") (pintype "bidirectional"))
      (node (ref "R4") (pin "1") (pinfunction "1_1") (pintype "passive"))
    )
    (net (code "49") (name "Net-(IC2-Y3)") (class "Default")
      (node (ref "IC2") (pin "P$7") (pinfunction "Y3_P$7") (pintype "bidirectional"))
      (node (ref "R5") (pin "1") (pinfunction "1_1") (pintype "passive"))
    )
    (net (code "50") (name "Net-(IC2-Y4)") (class "Default")
      (node (ref "IC2") (pin "P$8") (pinfunction "Y4_P$8") (pintype "bidirectional"))
      (node (ref "R6") (pin "1") (pinfunction "1_1") (pintype "passive"))
    )
    (net (code "51") (name "Net-(IC3-Y1)") (class "Default")
      (node (ref "IC3") (pin "P$3") (pinfunction "Y1_P$3") (pintype "bidirectional"))
      (node (ref "R7") (pin "1") (pinfunction "1_1") (pintype "passive"))
    )
    (net (code "52") (name "Net-(IC3-Y2)") (class "Default")
      (node (ref "IC3") (pin "P$5") (pinfunction "Y2_P$5") (pintype "bidirectional"))
      (node (ref "R8") (pin "1") (pinfunction "1_1") (pintype "passive"))
    )
    (net (code "53") (name "Net-(IC3-Y3)") (class "Default")
      (node (ref "IC3") (pin "P$7") (pinfunction "Y3_P$7") (pintype "bidirectional"))
      (node (ref "R9") (pin "1") (pinfunction "1_1") (pintype "passive"))
    )
    (net (code "54") (name "Net-(IC3-Y4)") (class "Default")
      (node (ref "IC3") (pin "P$8") (pinfunction "Y4_P$8") (pintype "bidirectional"))
      (node (ref "R10") (pin "1") (pinfunction "1_1") (pintype "passive"))
    )
    (net (code "55") (name "Net-(IC4-Y1)") (class "Default")
      (node (ref "IC4") (pin "P$3") (pinfunction "Y1_P$3") (pintype "bidirectional"))
      (node (ref "R11") (pin "1") (pinfunction "1_1") (pintype "passive"))
    )
    (net (code "56") (name "Net-(IC4-Y2)") (class "Default")
      (node (ref "IC4") (pin "P$5") (pinfunction "Y2_P$5") (pintype "bidirectional"))
      (node (ref "R12") (pin "1") (pinfunction "1_1") (pintype "passive"))
    )
    (net (code "57") (name "Net-(IC4-Y3)") (class "Default")
      (node (ref "IC4") (pin "P$7") (pinfunction "Y3_P$7") (pintype "bidirectional"))
      (node (ref "R13") (pin "1") (pinfunction "1_1") (pintype "passive"))
    )
    (net (code "58") (name "Net-(IC4-Y4)") (class "Default")
      (node (ref "IC4") (pin "P$8") (pinfunction "Y4_P$8") (pintype "bidirectional"))
      (node (ref "R14") (pin "1") (pinfunction "1_1") (pintype "passive"))
    )
    (net (code "59") (name "Net-(IC5-Y1)") (class "Default")
      (node (ref "IC5") (pin "P$3") (pinfunction "Y1_P$3") (pintype "bidirectional"))
      (node (ref "R15") (pin "1") (pinfunction "1_1") (pintype "passive"))
    )
    (net (code "60") (name "Net-(IC5-Y2)") (class "Default")
      (node (ref "IC5") (pin "P$8") (pinfunction "Y2_P$8") (pintype "bidirectional"))
      (node (ref "R16") (pin "1") (pinfunction "1_1") (pintype "passive"))
    )
    (net (code "61") (name "Net-(IC6-CBOOT)") (class "Default")
      (node (ref "C22") (pin "1") (pinfunction "1_1") (pintype "passive"))
      (node (ref "IC6") (pin "P$3") (pinfunction "CBOOT_P$3") (pintype "bidirectional"))
    )
    (net (code "62") (name "Net-(IC6-EN)") (class "Default")
      (node (ref "C6") (pin "1") (pinfunction "1_1") (pintype "passive"))
      (node (ref "IC6") (pin "P$12") (pinfunction "EN_P$12") (pintype "bidirectional"))
      (node (ref "R1") (pin "2") (pinfunction "2_2") (pintype "passive"))
      (node (ref "R2") (pin "2") (pinfunction "2_2") (pintype "passive"))
    )
    (net (code "63") (name "Net-(IC6-FB)") (class "Default")
      (node (ref "C24") (pin "2") (pinfunction "2_2") (pintype "passive"))
      (node (ref "IC6") (pin "P$9") (pinfunction "FB_P$9") (pintype "bidirectional"))
      (node (ref "R29") (pin "2") (pinfunction "2_2") (pintype "passive"))
      (node (ref "R30") (pin "1") (pinfunction "1_1") (pintype "passive"))
    )
    (net (code "64") (name "Net-(IC6-VCC)") (class "Default")
      (node (ref "C18") (pin "1") (pinfunction "1_1") (pintype "passive"))
      (node (ref "IC6") (pin "P$4") (pinfunction "VCC_P$4") (pintype "bidirectional"))
    )
    (net (code "65") (name "Net-(IC7-Y1)") (class "Default")
      (node (ref "IC7") (pin "P$3") (pinfunction "Y1_P$3") (pintype "bidirectional"))
      (node (ref "R17") (pin "1") (pinfunction "1_1") (pintype "passive"))
    )
    (net (code "66") (name "Net-(IC7-Y2)") (class "Default")
      (node (ref "IC7") (pin "P$5") (pinfunction "Y2_P$5") (pintype "bidirectional"))
      (node (ref "R18") (pin "1") (pinfunction "1_1") (pintype "passive"))
    )
    (net (code "67") (name "Net-(IC7-Y3)") (class "Default")
      (node (ref "IC7") (pin "P$7") (pinfunction "Y3_P$7") (pintype "bidirectional"))
      (node (ref "R19") (pin "1") (pinfunction "1_1") (pintype "passive"))
    )
    (net (code "68") (name "Net-(IC7-Y4)") (class "Default")
      (node (ref "IC7") (pin "P$8") (pinfunction "Y4_P$8") (pintype "bidirectional"))
      (node (ref "R20") (pin "1") (pinfunction "1_1") (pintype "passive"))
    )
    (net (code "69") (name "Net-(IC8-Y1)") (class "Default")
      (node (ref "IC8") (pin "P$3") (pinfunction "Y1_P$3") (pintype "bidirectional"))
      (node (ref "R21") (pin "1") (pinfunction "1_1") (pintype "passive"))
    )
    (net (code "70") (name "Net-(IC8-Y2)") (class "Default")
      (node (ref "IC8") (pin "P$5") (pinfunction "Y2_P$5") (pintype "bidirectional"))
      (node (ref "R22") (pin "1") (pinfunction "1_1") (pintype "passive"))
    )
    (net (code "71") (name "Net-(IC8-Y3)") (class "Default")
      (node (ref "IC8") (pin "P$7") (pinfunction "Y3_P$7") (pintype "bidirectional"))
      (node (ref "R23") (pin "1") (pinfunction "1_1") (pintype "passive"))
    )
    (net (code "72") (name "Net-(IC8-Y4)") (class "Default")
      (node (ref "IC8") (pin "P$8") (pinfunction "Y4_P$8") (pintype "bidirectional"))
      (node (ref "R24") (pin "1") (pinfunction "1_1") (pintype "passive"))
    )
    (net (code "73") (name "Net-(IC9-Y1)") (class "Default")
      (node (ref "IC9") (pin "P$3") (pinfunction "Y1_P$3") (pintype "bidirectional"))
      (node (ref "R25") (pin "1") (pinfunction "1_1") (pintype "passive"))
    )
    (net (code "74") (name "Net-(IC9-Y2)") (class "Default")
      (node (ref "IC9") (pin "P$5") (pinfunction "Y2_P$5") (pintype "bidirectional"))
      (node (ref "R26") (pin "1") (pinfunction "1_1") (pintype "passive"))
    )
    (net (code "75") (name "Net-(IC9-Y3)") (class "Default")
      (node (ref "IC9") (pin "P$7") (pinfunction "Y3_P$7") (pintype "bidirectional"))
      (node (ref "R27") (pin "1") (pinfunction "1_1") (pintype "passive"))
    )
    (net (code "76") (name "Net-(IC9-Y4)") (class "Default")
      (node (ref "IC9") (pin "P$8") (pinfunction "Y4_P$8") (pintype "bidirectional"))
      (node (ref "R28") (pin "1") (pinfunction "1_1") (pintype "passive"))
    )
    (net (code "77") (name "Net-(IC11-BCK)") (class "Default")
      (node (ref "IC11") (pin "P$2") (pinfunction "BCK_P$2") (pintype "bidirectional"))
      (node (ref "R21") (pin "2") (pinfunction "2_2") (pintype "passive"))
    )
    (net (code "78") (name "Net-(IC11-LRCLK)") (class "Default")
      (node (ref "IC11") (pin "P$4") (pinfunction "LRCLK_P$4") (pintype "bidirectional"))
      (node (ref "R25") (pin "2") (pinfunction "2_2") (pintype "passive"))
    )
    (net (code "79") (name "Net-(IC11-SCK)") (class "Default")
      (node (ref "IC11") (pin "P$1") (pinfunction "SCK_P$1") (pintype "bidirectional"))
      (node (ref "R17") (pin "2") (pinfunction "2_2") (pintype "passive"))
    )
    (net (code "80") (name "Net-(IC11-VIN)") (class "Default")
      (node (ref "C27") (pin "1") (pinfunction "1_1") (pintype "passive"))
      (node (ref "IC11") (pin "P$6") (pinfunction "VIN_P$6") (pintype "bidirectional"))
      (node (ref "SV14") (pin "2") (pinfunction "2_2") (pintype "passive"))
    )
    (net (code "81") (name "Net-(IC12-BCK)") (class "Default")
      (node (ref "IC12") (pin "P$2") (pinfunction "BCK_P$2") (pintype "bidirectional"))
      (node (ref "R22") (pin "2") (pinfunction "2_2") (pintype "passive"))
    )
    (net (code "82") (name "Net-(IC12-LRCLK)") (class "Default")
      (node (ref "IC12") (pin "P$4") (pinfunction "LRCLK_P$4") (pintype "bidirectional"))
      (node (ref "R26") (pin "2") (pinfunction "2_2") (pintype "passive"))
    )
    (net (code "83") (name "Net-(IC12-SCK)") (class "Default")
      (node (ref "IC12") (pin "P$1") (pinfunction "SCK_P$1") (pintype "bidirectional"))
      (node (ref "R18") (pin "2") (pinfunction "2_2") (pintype "passive"))
    )
    (net (code "84") (name "Net-(IC12-VIN)") (class "Default")
      (node (ref "C28") (pin "1") (pinfunction "1_1") (pintype "passive"))
      (node (ref "IC12") (pin "P$6") (pinfunction "VIN_P$6") (pintype "bidirectional"))
      (node (ref "SV15") (pin "2") (pinfunction "2_2") (pintype "passive"))
    )
    (net (code "85") (name "Net-(IC13-BCK)") (class "Default")
      (node (ref "IC13") (pin "P$2") (pinfunction "BCK_P$2") (pintype "bidirectional"))
      (node (ref "R23") (pin "2") (pinfunction "2_2") (pintype "passive"))
    )
    (net (code "86") (name "Net-(IC13-LRCLK)") (class "Default")
      (node (ref "IC13") (pin "P$4") (pinfunction "LRCLK_P$4") (pintype "bidirectional"))
      (node (ref "R27") (pin "2") (pinfunction "2_2") (pintype "passive"))
    )
    (net (code "87") (name "Net-(IC13-SCK)") (class "Default")
      (node (ref "IC13") (pin "P$1") (pinfunction "SCK_P$1") (pintype "bidirectional"))
      (node (ref "R19") (pin "2") (pinfunction "2_2") (pintype "passive"))
    )
    (net (code "88") (name "Net-(IC13-VIN)") (class "Default")
      (node (ref "C29") (pin "1") (pinfunction "1_1") (pintype "passive"))
      (node (ref "IC13") (pin "P$6") (pinfunction "VIN_P$6") (pintype "bidirectional"))
      (node (ref "SV16") (pin "2") (pinfunction "2_2") (pintype "passive"))
    )
    (net (code "89") (name "Net-(IC14-BCK)") (class "Default")
      (node (ref "IC14") (pin "P$2") (pinfunction "BCK_P$2") (pintype "bidirectional"))
      (node (ref "R24") (pin "2") (pinfunction "2_2") (pintype "passive"))
    )
    (net (code "90") (name "Net-(IC14-LRCLK)") (class "Default")
      (node (ref "IC14") (pin "P$4") (pinfunction "LRCLK_P$4") (pintype "bidirectional"))
      (node (ref "R28") (pin "2") (pinfunction "2_2") (pintype "passive"))
    )
    (net (code "91") (name "Net-(IC14-SCK)") (class "Default")
      (node (ref "IC14") (pin "P$1") (pinfunction "SCK_P$1") (pintype "bidirectional"))
      (node (ref "R20") (pin "2") (pinfunction "2_2") (pintype "passive"))
    )
    (net (code "92") (name "Net-(IC14-VIN)") (class "Default")
      (node (ref "C30") (pin "1") (pinfunction "1_1") (pintype "passive"))
      (node (ref "IC14") (pin "P$6") (pinfunction "VIN_P$6") (pintype "bidirectional"))
      (node (ref "SV17") (pin "2") (pinfunction "2_2") (pintype "passive"))
    )
    (net (code "93") (name "Net-(IC15-CLK)") (class "Default")
      (node (ref "IC15") (pin "P$9") (pinfunction "CLK_P$9") (pintype "bidirectional"))
      (node (ref "R10") (pin "2") (pinfunction "2_2") (pintype "passive"))
      (node (ref "SV6") (pin "4") (pinfunction "4_4") (pintype "passive"))
    )
    (net (code "94") (name "Net-(IC15-CSB)") (class "Default")
      (node (ref "IC15") (pin "P$10") (pinfunction "CSB_P$10") (pintype "bidirectional"))
      (node (ref "R11") (pin "2") (pinfunction "2_2") (pintype "passive"))
      (node (ref "SV6") (pin "5") (pinfunction "5_5") (pintype "passive"))
    )
    (net (code "95") (name "Net-(IC15-SPIPCM)") (class "Default")
      (node (ref "IC15") (pin "P$11") (pinfunction "SPIPCM_P$11") (pintype "bidirectional"))
      (node (ref "R33") (pin "2") (pinfunction "2_2") (pintype "passive"))
    )
    (net (code "96") (name "Net-(LED1-PadC)") (class "Default")
      (node (ref "LED1") (pin "C") (pinfunction "C_C") (pintype "passive"))
      (node (ref "R31") (pin "1") (pinfunction "1_1") (pintype "passive"))
    )
    (net (code "97") (name "Net-(LED2-PadC)") (class "Default")
      (node (ref "LED2") (pin "C") (pinfunction "C_C") (pintype "passive"))
      (node (ref "R32") (pin "1") (pinfunction "1_1") (pintype "passive"))
    )
    (net (code "98") (name "Net-(R3-Pad2)") (class "Default")
      (node (ref "R3") (pin "2") (pinfunction "2_2") (pintype "passive"))
      (node (ref "SV9") (pin "3") (pinfunction "3_3") (pintype "passive"))
    )
    (net (code "99") (name "Net-(R4-Pad2)") (class "Default")
      (node (ref "R4") (pin "2") (pinfunction "2_2") (pintype "passive"))
      (node (ref "SV10") (pin "3") (pinfunction "3_3") (pintype "passive"))
    )
    (net (code "100") (name "Net-(R5-Pad2)") (class "Default")
      (node (ref "R5") (pin "2") (pinfunction "2_2") (pintype "passive"))
      (node (ref "SV11") (pin "3") (pinfunction "3_3") (pintype "passive"))
    )
    (net (code "101") (name "Net-(R6-Pad2)") (class "Default")
      (node (ref "R6") (pin "2") (pinfunction "2_2") (pintype "passive"))
      (node (ref "SV6") (pin "3") (pinfunction "3_3") (pintype "passive"))
    )
    (net (code "102") (name "Net-(R7-Pad2)") (class "Default")
      (node (ref "R7") (pin "2") (pinfunction "2_2") (pintype "passive"))
      (node (ref "SV9") (pin "4") (pinfunction "4_4") (pintype "passive"))
    )
    (net (code "103") (name "Net-(R8-Pad2)") (class "Default")
      (node (ref "R8") (pin "2") (pinfunction "2_2") (pintype "passive"))
      (node (ref "SV10") (pin "4") (pinfunction "4_4") (pintype "passive"))
    )
    (net (code "104") (name "Net-(R9-Pad2)") (class "Default")
      (node (ref "R9") (pin "2") (pinfunction "2_2") (pintype "passive"))
      (node (ref "SV11") (pin "4") (pinfunction "4_4") (pintype "passive"))
    )
    (net (code "105") (name "Net-(R12-Pad2)") (class "Default")
      (node (ref "R12") (pin "2") (pinfunction "2_2") (pintype "passive"))
      (node (ref "SV9") (pin "5") (pinfunction "5_5") (pintype "passive"))
    )
    (net (code "106") (name "Net-(R13-Pad2)") (class "Default")
      (node (ref "R13") (pin "2") (pinfunction "2_2") (pintype "passive"))
      (node (ref "SV11") (pin "5") (pinfunction "5_5") (pintype "passive"))
    )
    (net (code "107") (name "Net-(R14-Pad2)") (class "Default")
      (node (ref "R14") (pin "2") (pinfunction "2_2") (pintype "passive"))
      (node (ref "SV10") (pin "5") (pinfunction "5_5") (pintype "passive"))
    )
    (net (code "108") (name "VCC") (class "Default")
      (node (ref "C23") (pin "1") (pinfunction "1_1") (pintype "passive"))
      (node (ref "C24") (pin "1") (pinfunction "1_1") (pintype "passive"))
      (node (ref "C25") (pin "1") (pinfunction "1_1") (pintype "passive"))
      (node (ref "C26") (pin "1") (pinfunction "1_1") (pintype "passive"))
      (node (ref "IC10") (pin "1") (pinfunction "IN_1") (pintype "input"))
      (node (ref "IC16") (pin "VIN10ER") (pinfunction "VCC_VIN10ER") (pintype "bidirectional"))
      (node (ref "IC16") (pin "VIN@2") (pinfunction "VCC_VIN@2") (pintype "bidirectional"))
      (node (ref "IC6") (pin "P$5") (pinfunction "BIAS_P$5") (pintype "bidirectional"))
      (node (ref "L1") (pin "2") (pinfunction "2_2") (pintype "passive"))
      (node (ref "LED1") (pin "A") (pinfunction "A_A") (pintype "passive"))
      (node (ref "R29") (pin "1") (pinfunction "1_1") (pintype "passive"))
      (node (ref "SV12") (pin "3") (pinfunction "3_3") (pintype "passive"))
      (node (ref "SV14") (pin "3") (pinfunction "3_3") (pintype "passive"))
      (node (ref "SV15") (pin "3") (pinfunction "3_3") (pintype "passive"))
      (node (ref "SV16") (pin "3") (pinfunction "3_3") (pintype "passive"))
      (node (ref "SV17") (pin "3") (pinfunction "3_3") (pintype "passive"))
      (node (ref "SV4") (pin "3") (pinfunction "3_3") (pintype "passive"))
      (node (ref "SV5") (pin "3") (pinfunction "3_3") (pintype "passive"))
      (node (ref "SV7") (pin "3") (pinfunction "3_3") (pintype "passive"))
    )
    (net (code "109") (name "unconnected-(IC6-PGOOD-PadP$8)") (class "Default")
      (node (ref "IC6") (pin "P$8") (pinfunction "PGOOD_P$8") (pintype "bidirectional"))
    )
    (net (code "110") (name "unconnected-(IC6-RT-PadP$7)") (class "Default")
      (node (ref "IC6") (pin "P$7") (pinfunction "RT_P$7") (pintype "bidirectional"))
    )
    (net (code "111") (name "unconnected-(IC6-SS{slash}TRK-PadP$11)") (class "Default")
      (node (ref "IC6") (pin "P$11") (pinfunction "SS/TRK_P$11") (pintype "bidirectional"))
    )
    (net (code "112") (name "unconnected-(IC15-1V6-PadP$28)") (class "Default")
      (node (ref "IC15") (pin "P$28") (pinfunction "1V6_P$28") (pintype "bidirectional"))
    )
    (net (code "113") (name "unconnected-(IC15-A100-PadP$24)") (class "Default")
      (node (ref "IC15") (pin "P$24") (pinfunction "A100_P$24") (pintype "bidirectional"))
    )
    (net (code "114") (name "unconnected-(IC15-EXT-PadP$4)") (class "Default")
      (node (ref "IC15") (pin "P$4") (pinfunction "EXT_P$4") (pintype "bidirectional"))
    )
    (net (code "115") (name "unconnected-(IC15-L18N-PadP$35)") (class "Default")
      (node (ref "IC15") (pin "P$35") (pinfunction "L18N_P$35") (pintype "bidirectional"))
    )
    (net (code "116") (name "unconnected-(IC15-L18P-PadP$36)") (class "Default")
      (node (ref "IC15") (pin "P$36") (pinfunction "L18P_P$36") (pintype "bidirectional"))
    )
    (net (code "117") (name "unconnected-(IC15-LED0-PadP$29)") (class "Default")
      (node (ref "IC15") (pin "P$29") (pinfunction "LED0_P$29") (pintype "bidirectional"))
    )
    (net (code "118") (name "unconnected-(IC15-LED1-PadP$30)") (class "Default")
      (node (ref "IC15") (pin "P$30") (pinfunction "LED1_P$30") (pintype "bidirectional"))
    )
    (net (code "119") (name "unconnected-(IC15-LED2-PadP$31)") (class "Default")
      (node (ref "IC15") (pin "P$31") (pinfunction "LED2_P$31") (pintype "bidirectional"))
    )
    (net (code "120") (name "unconnected-(IC15-LN-PadP$39)") (class "Default")
      (node (ref "IC15") (pin "P$39") (pinfunction "LN_P$39") (pintype "bidirectional"))
    )
    (net (code "121") (name "unconnected-(IC15-LP-PadP$40)") (class "Default")
      (node (ref "IC15") (pin "P$40") (pinfunction "LP_P$40") (pintype "bidirectional"))
    )
    (net (code "122") (name "unconnected-(IC15-M+-PadP$20)") (class "Default")
      (node (ref "IC15") (pin "P$20") (pinfunction "M+_P$20") (pintype "bidirectional"))
    )
    (net (code "123") (name "unconnected-(IC15-M+-PadP$22)") (class "Default")
      (node (ref "IC15") (pin "P$22") (pinfunction "M+_P$22") (pintype "bidirectional"))
    )
    (net (code "124") (name "unconnected-(IC15-M--PadP$19)") (class "Default")
      (node (ref "IC15") (pin "P$19") (pinfunction "M-_P$19") (pintype "bidirectional"))
    )
    (net (code "125") (name "unconnected-(IC15-M--PadP$21)") (class "Default")
      (node (ref "IC15") (pin "P$21") (pinfunction "M-_P$21") (pintype "bidirectional"))
    )
    (net (code "126") (name "unconnected-(IC15-MFB-PadP$27)") (class "Default")
      (node (ref "IC15") (pin "P$27") (pinfunction "MFB_P$27") (pintype "bidirectional"))
    )
    (net (code "127") (name "unconnected-(IC15-MICAN-PadP$32)") (class "Default")
      (node (ref "IC15") (pin "P$32") (pinfunction "MICAN_P$32") (pintype "bidirectional"))
    )
    (net (code "128") (name "unconnected-(IC15-MICAP-PadP$33)") (class "Default")
      (node (ref "IC15") (pin "P$33") (pinfunction "MICAP_P$33") (pintype "bidirectional"))
    )
    (net (code "129") (name "unconnected-(IC15-MICB-PadP$34)") (class "Default")
      (node (ref "IC15") (pin "P$34") (pinfunction "MICB_P$34") (pintype "bidirectional"))
    )
    (net (code "130") (name "unconnected-(IC15-MOSI-PadP$12)") (class "Default")
      (node (ref "IC15") (pin "P$12") (pinfunction "MOSI_P$12") (pintype "bidirectional"))
    )
    (net (code "131") (name "unconnected-(IC15-MUTE-PadP$17)") (class "Default")
      (node (ref "IC15") (pin "P$17") (pinfunction "MUTE_P$17") (pintype "bidirectional"))
    )
    (net (code "132") (name "unconnected-(IC15-NC-PadP$43)") (class "Default")
      (node (ref "IC15") (pin "P$43") (pinfunction "NC_P$43") (pintype "bidirectional"))
    )
    (net (code "133") (name "unconnected-(IC15-N{slash}V+-PadP$16)") (class "Default")
      (node (ref "IC15") (pin "P$16") (pinfunction "N/V+_P$16") (pintype "bidirectional"))
    )
    (net (code "134") (name "unconnected-(IC15-P100-PadP$26)") (class "Default")
      (node (ref "IC15") (pin "P$26") (pinfunction "P100_P$26") (pintype "bidirectional"))
    )
    (net (code "135") (name "unconnected-(IC15-P101-PadP$25)") (class "Default")
      (node (ref "IC15") (pin "P$25") (pinfunction "P101_P$25") (pintype "bidirectional"))
    )
    (net (code "136") (name "unconnected-(IC15-P107-PadP$18)") (class "Default")
      (node (ref "IC15") (pin "P$18") (pinfunction "P107_P$18") (pintype "bidirectional"))
    )
    (net (code "137") (name "unconnected-(IC15-P1016-PadP$41)") (class "Default")
      (node (ref "IC15") (pin "P$41") (pinfunction "P1016_P$41") (pintype "bidirectional"))
    )
    (net (code "138") (name "unconnected-(IC15-P1017-PadP$42)") (class "Default")
      (node (ref "IC15") (pin "P$42") (pinfunction "P1017_P$42") (pintype "bidirectional"))
    )
    (net (code "139") (name "unconnected-(IC15-PLY-PadP$13)") (class "Default")
      (node (ref "IC15") (pin "P$13") (pinfunction "PLY_P$13") (pintype "bidirectional"))
    )
    (net (code "140") (name "unconnected-(IC15-P{slash}V--PadP$15)") (class "Default")
      (node (ref "IC15") (pin "P$15") (pinfunction "P/V-_P$15") (pintype "bidirectional"))
    )
    (net (code "141") (name "unconnected-(IC15-RN-PadP$37)") (class "Default")
      (node (ref "IC15") (pin "P$37") (pinfunction "RN_P$37") (pintype "bidirectional"))
    )
    (net (code "142") (name "unconnected-(IC15-RP-PadP$38)") (class "Default")
      (node (ref "IC15") (pin "P$38") (pinfunction "RP_P$38") (pintype "bidirectional"))
    )
    (net (code "143") (name "unconnected-(IC15-RST-PadP$8)") (class "Default")
      (node (ref "IC15") (pin "P$8") (pinfunction "RST_P$8") (pintype "bidirectional"))
    )
    (net (code "144") (name "unconnected-(IC15-SENS-PadP$3)") (class "Default")
      (node (ref "IC15") (pin "P$3") (pinfunction "SENS_P$3") (pintype "bidirectional"))
    )
    (net (code "145") (name "unconnected-(IC15-TWS-PadP$14)") (class "Default")
      (node (ref "IC15") (pin "P$14") (pinfunction "TWS_P$14") (pintype "bidirectional"))
    )
    (net (code "146") (name "unconnected-(IC15-USB3V3-PadP$44)") (class "Default")
      (node (ref "IC15") (pin "P$44") (pinfunction "USB3V3_P$44") (pintype "bidirectional"))
    )
    (net (code "147") (name "unconnected-(IC15-USBN-PadP$2)") (class "Default")
      (node (ref "IC15") (pin "P$2") (pinfunction "USBN_P$2") (pintype "bidirectional"))
    )
    (net (code "148") (name "unconnected-(IC15-USBP-PadP$23)") (class "Default")
      (node (ref "IC15") (pin "P$23") (pinfunction "USBP_P$23") (pintype "bidirectional"))
    )
    (net (code "149") (name "unconnected-(IC15-VCHG-PadP$1)") (class "Default")
      (node (ref "IC15") (pin "P$1") (pinfunction "VCHG_P$1") (pintype "bidirectional"))
    )
    (net (code "150") (name "unconnected-(IC16A-NC-Pad3V320ER)") (class "Default")
      (node (ref "IC16") (pin "3V320ER") (pinfunction "NC_3V320ER") (pintype "bidirectional"))
    )
    (net (code "151") (name "unconnected-(IC16D-3V3-Pad3V310ER)") (class "Default")
      (node (ref "IC16") (pin "3V310ER") (pinfunction "3V3_3V310ER") (pintype "bidirectional"))
    )
    (net (code "152") (name "unconnected-(SV1-Pad2)") (class "Default")
      (node (ref "SV1") (pin "2") (pinfunction "2_2") (pintype "passive"))
    )
    (net (code "153") (name "unconnected-(SV1-Pad3)") (class "Default")
      (node (ref "SV1") (pin "3") (pinfunction "3_3") (pintype "passive"))
    )
    (net (code "154") (name "unconnected-(SV1-Pad4)") (class "Default")
      (node (ref "SV1") (pin "4") (pinfunction "4_4") (pintype "passive"))
    )
    (net (code "155") (name "unconnected-(SV1-Pad5)") (class "Default")
      (node (ref "SV1") (pin "5") (pinfunction "5_5") (pintype "passive"))
    )
    (net (code "156") (name "unconnected-(SV1-Pad6)") (class "Default")
      (node (ref "SV1") (pin "6") (pinfunction "6_6") (pintype "passive"))
    )
    (net (code "157") (name "unconnected-(SV1-Pad9)") (class "Default")
      (node (ref "SV1") (pin "9") (pinfunction "9_9") (pintype "passive"))
    )
    (net (code "158") (name "unconnected-(SV1-Pad10)") (class "Default")
      (node (ref "SV1") (pin "10") (pinfunction "10_10") (pintype "passive"))
    )
    (net (code "159") (name "unconnected-(SV1-Pad11)") (class "Default")
      (node (ref "SV1") (pin "11") (pinfunction "11_11") (pintype "passive"))
    )
    (net (code "160") (name "unconnected-(SV1-Pad12)") (class "Default")
      (node (ref "SV1") (pin "12") (pinfunction "12_12") (pintype "passive"))
    )
    (net (code "161") (name "unconnected-(SV1-Pad13)") (class "Default")
      (node (ref "SV1") (pin "13") (pinfunction "13_13") (pintype "passive"))
    )
    (net (code "162") (name "unconnected-(SV1-Pad14)") (class "Default")
      (node (ref "SV1") (pin "14") (pinfunction "14_14") (pintype "passive"))
    )
    (net (code "163") (name "unconnected-(SV1-Pad15)") (class "Default")
      (node (ref "SV1") (pin "15") (pinfunction "15_15") (pintype "passive"))
    )
    (net (code "164") (name "unconnected-(SV1-Pad16)") (class "Default")
      (node (ref "SV1") (pin "16") (pinfunction "16_16") (pintype "passive"))
    )
    (net (code "165") (name "unconnected-(SV1-Pad17)") (class "Default")
      (node (ref "SV1") (pin "17") (pinfunction "17_17") (pintype "passive"))
    )
    (net (code "166") (name "unconnected-(SV1-Pad18)") (class "Default")
      (node (ref "SV1") (pin "18") (pinfunction "18_18") (pintype "passive"))
    )
    (net (code "167") (name "unconnected-(SV1-Pad19)") (class "Default")
      (node (ref "SV1") (pin "19") (pinfunction "19_19") (pintype "passive"))
    )
    (net (code "168") (name "unconnected-(SV1-Pad20)") (class "Default")
      (node (ref "SV1") (pin "20") (pinfunction "20_20") (pintype "passive"))
    )
  )
)
